# FT232_BreakOutBoard.net
KiCad netlist of a schematic drawn in EAGLE
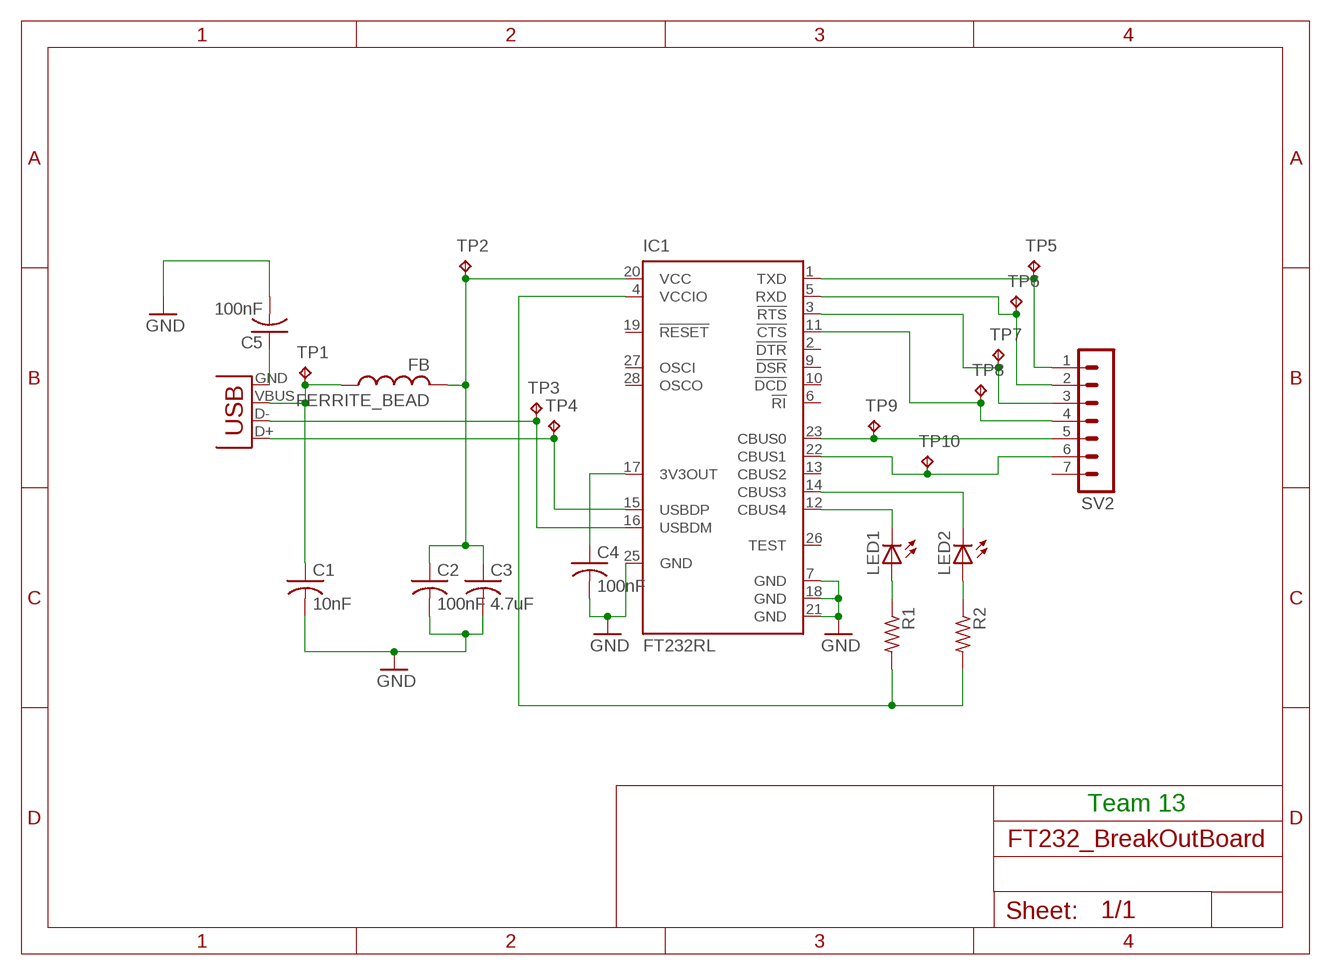
[diagram p0: schematic, sheet 1]

(export (version "E")
  (design (tool "Eeschema 10.0.6"))
  (components
    (comp (ref "C1")
      (value "10nF")
      (footprint "eagle-import:C0805")
      (libsource (lib "eagle-import") (part "C-USC0805"))
    )
    (comp (ref "C2")
      (value "100nF")
      (footprint "eagle-import:C0805")
      (libsource (lib "eagle-import") (part "C-USC0805"))
    )
    (comp (ref "C3")
      (value "4.7uF")
      (footprint "eagle-import:C0805")
      (libsource (lib "eagle-import") (part "C-USC0805"))
    )
    (comp (ref "C4")
      (value "100nF")
      (footprint "eagle-import:C0805")
      (libsource (lib "eagle-import") (part "C-USC0805"))
    )
    (comp (ref "C5")
      (value "100nF")
      (footprint "eagle-import:C0805")
      (libsource (lib "eagle-import") (part "C-USC0805"))
    )
    (comp (ref "FERRITE_BEAD")
      (value "FB")
      (footprint "eagle-import:FB")
      (libsource (lib "eagle-import") (part "FB"))
    )
    (comp (ref "IC1")
      (value "FT232RL")
      (footprint "eagle-import:SSOP28")
      (libsource (lib "eagle-import") (part "FT232RL"))
    )
    (comp (ref "LED1")
      (value "LEDCHIPLED_0805")
      (footprint "eagle-import:CHIPLED_0805")
      (libsource (lib "eagle-import") (part "LEDCHIPLED_0805"))
    )
    (comp (ref "LED2")
      (value "LEDCHIPLED_0805")
      (footprint "eagle-import:CHIPLED_0805")
      (libsource (lib "eagle-import") (part "LEDCHIPLED_0805"))
    )
    (comp (ref "R1")
      (value "R-US_R0805")
      (footprint "eagle-import:R0805")
      (libsource (lib "eagle-import") (part "R-US_R0805"))
    )
    (comp (ref "R2")
      (value "R-US_R0805")
      (footprint "eagle-import:R0805")
      (libsource (lib "eagle-import") (part "R-US_R0805"))
    )
    (comp (ref "SV2")
      (value "MA07-1")
      (footprint "eagle-import:MA07-1")
      (libsource (lib "eagle-import") (part "MA07-1"))
    )
    (comp (ref "TP1")
      (value "TPB1,27")
      (footprint "eagle-import:B1,27")
      (libsource (lib "eagle-import") (part "TPB1,27"))
    )
    (comp (ref "TP2")
      (value "TPB1,27")
      (footprint "eagle-import:B1,27")
      (libsource (lib "eagle-import") (part "TPB1,27"))
    )
    (comp (ref "TP3")
      (value "TPB1,27")
      (footprint "eagle-import:B1,27")
      (libsource (lib "eagle-import") (part "TPB1,27"))
    )
    (comp (ref "TP4")
      (value "TPB1,27")
      (footprint "eagle-import:B1,27")
      (libsource (lib "eagle-import") (part "TPB1,27"))
    )
    (comp (ref "TP5")
      (value "TPB1,27")
      (footprint "eagle-import:B1,27")
      (libsource (lib "eagle-import") (part "TPB1,27"))
    )
    (comp (ref "TP6")
      (value "TPB1,27")
      (footprint "eagle-import:B1,27")
      (libsource (lib "eagle-import") (part "TPB1,27"))
    )
    (comp (ref "TP7")
      (value "TPB1,27")
      (footprint "eagle-import:B1,27")
      (libsource (lib "eagle-import") (part "TPB1,27"))
    )
    (comp (ref "TP8")
      (value "TPB1,27")
      (footprint "eagle-import:B1,27")
      (libsource (lib "eagle-import") (part "TPB1,27"))
    )
    (comp (ref "TP9")
      (value "TPB1,27")
      (footprint "eagle-import:B1,27")
      (libsource (lib "eagle-import") (part "TPB1,27"))
    )
    (comp (ref "TP10")
      (value "TPB1,27")
      (footprint "eagle-import:B1,27")
      (libsource (lib "eagle-import") (part "TPB1,27"))
    )
    (comp (ref "X1")
      (value "USB-B-H")
      (footprint "eagle-import:USB-B-H")
      (libsource (lib "eagle-import") (part "USB-B-H"))
    )
  )
  (nets
    (net (code "1") (name "GND") (class "Default")
      (node (ref "C1") (pin "2") (pinfunction "2_2") (pintype "passive"))
      (node (ref "C2") (pin "2") (pinfunction "2_2") (pintype "passive"))
      (node (ref "C3") (pin "2") (pinfunction "2_2") (pintype "passive"))
      (node (ref "C4") (pin "2") (pinfunction "2_2") (pintype "passive"))
      (node (ref "C5") (pin "2") (pinfunction "2_2") (pintype "passive"))
      (node (ref "IC1") (pin "18") (pinfunction "GND_18") (pintype "power_in"))
      (node (ref "IC1") (pin "21") (pinfunction "GND_21") (pintype "power_in"))
      (node (ref "IC1") (pin "25") (pinfunction "GND_25") (pintype "power_in"))
      (node (ref "IC1") (pin "7") (pinfunction "GND_7") (pintype "power_in"))
    )
    (net (code "2") (name "Net-(C5-Pad1)") (class "Default")
      (node (ref "C5") (pin "1") (pinfunction "1_1") (pintype "passive"))
      (node (ref "X1") (pin "GND") (pinfunction "GND_GND") (pintype "bidirectional"))
    )
    (net (code "3") (name "Net-(FERRITE_BEAD-1)") (class "Default")
      (node (ref "C1") (pin "1") (pinfunction "1_1") (pintype "passive"))
      (node (ref "FERRITE_BEAD") (pin "P$1") (pinfunction "1_P$1") (pintype "passive"))
      (node (ref "TP1") (pin "TP") (pinfunction "TP_TP") (pintype "input"))
      (node (ref "X1") (pin "VBUS") (pinfunction "VBUS_VBUS") (pintype "bidirectional"))
    )
    (net (code "4") (name "Net-(FERRITE_BEAD-2)") (class "Default")
      (node (ref "C2") (pin "1") (pinfunction "1_1") (pintype "passive"))
      (node (ref "C3") (pin "1") (pinfunction "1_1") (pintype "passive"))
      (node (ref "FERRITE_BEAD") (pin "P$2") (pinfunction "2_P$2") (pintype "passive"))
      (node (ref "IC1") (pin "20") (pinfunction "VCC_20") (pintype "power_in"))
      (node (ref "TP2") (pin "TP") (pinfunction "TP_TP") (pintype "input"))
    )
    (net (code "5") (name "Net-(IC1-3V3OUT)") (class "Default")
      (node (ref "C4") (pin "1") (pinfunction "1_1") (pintype "passive"))
      (node (ref "IC1") (pin "17") (pinfunction "3V3OUT_17") (pintype "output"))
    )
    (net (code "6") (name "Net-(IC1-CBUS0)") (class "Default")
      (node (ref "IC1") (pin "23") (pinfunction "CBUS0_23") (pintype "bidirectional"))
      (node (ref "SV2") (pin "5") (pinfunction "5_5") (pintype "passive"))
      (node (ref "TP9") (pin "TP") (pinfunction "TP_TP") (pintype "input"))
    )
    (net (code "7") (name "Net-(IC1-CBUS1)") (class "Default")
      (node (ref "IC1") (pin "22") (pinfunction "CBUS1_22") (pintype "bidirectional"))
      (node (ref "SV2") (pin "6") (pinfunction "6_6") (pintype "passive"))
      (node (ref "TP10") (pin "TP") (pinfunction "TP_TP") (pintype "input"))
    )
    (net (code "8") (name "Net-(IC1-CBUS3)") (class "Default")
      (node (ref "IC1") (pin "14") (pinfunction "CBUS3_14") (pintype "bidirectional"))
      (node (ref "LED2") (pin "C") (pinfunction "C_C") (pintype "passive"))
    )
    (net (code "9") (name "Net-(IC1-CBUS4)") (class "Default")
      (node (ref "IC1") (pin "12") (pinfunction "CBUS4_12") (pintype "bidirectional"))
      (node (ref "LED1") (pin "C") (pinfunction "C_C") (pintype "passive"))
    )
    (net (code "10") (name "Net-(IC1-RXD)") (class "Default")
      (node (ref "IC1") (pin "5") (pinfunction "RXD_5") (pintype "input"))
      (node (ref "SV2") (pin "2") (pinfunction "2_2") (pintype "passive"))
      (node (ref "TP6") (pin "TP") (pinfunction "TP_TP") (pintype "input"))
    )
    (net (code "11") (name "Net-(IC1-TXD)") (class "Default")
      (node (ref "IC1") (pin "1") (pinfunction "TXD_1") (pintype "output"))
      (node (ref "SV2") (pin "1") (pinfunction "1_1") (pintype "passive"))
      (node (ref "TP5") (pin "TP") (pinfunction "TP_TP") (pintype "input"))
    )
    (net (code "12") (name "Net-(IC1-USBDM)") (class "Default")
      (node (ref "IC1") (pin "16") (pinfunction "USBDM_16") (pintype "bidirectional"))
      (node (ref "TP3") (pin "TP") (pinfunction "TP_TP") (pintype "input"))
      (node (ref "X1") (pin "D-") (pinfunction "D-_D-") (pintype "bidirectional"))
    )
    (net (code "13") (name "Net-(IC1-USBDP)") (class "Default")
      (node (ref "IC1") (pin "15") (pinfunction "USBDP_15") (pintype "bidirectional"))
      (node (ref "TP4") (pin "TP") (pinfunction "TP_TP") (pintype "input"))
      (node (ref "X1") (pin "D+") (pinfunction "D+_D+") (pintype "bidirectional"))
    )
    (net (code "14") (name "Net-(IC1-VCCIO)") (class "Default")
      (node (ref "IC1") (pin "4") (pinfunction "VCCIO_4") (pintype "power_in"))
      (node (ref "R1") (pin "2") (pinfunction "2_2") (pintype "passive"))
      (node (ref "R2") (pin "2") (pinfunction "2_2") (pintype "passive"))
    )
    (net (code "15") (name "Net-(IC1-~{CTS})") (class "Default")
      (node (ref "IC1") (pin "11") (pinfunction "~{CTS}_11") (pintype "input"))
      (node (ref "SV2") (pin "4") (pinfunction "4_4") (pintype "passive"))
      (node (ref "TP8") (pin "TP") (pinfunction "TP_TP") (pintype "input"))
    )
    (net (code "16") (name "Net-(IC1-~{RTS})") (class "Default")
      (node (ref "IC1") (pin "3") (pinfunction "~{RTS}_3") (pintype "output"))
      (node (ref "SV2") (pin "3") (pinfunction "3_3") (pintype "passive"))
      (node (ref "TP7") (pin "TP") (pinfunction "TP_TP") (pintype "input"))
    )
    (net (code "17") (name "Net-(LED1-PadA)") (class "Default")
      (node (ref "LED1") (pin "A") (pinfunction "A_A") (pintype "passive"))
      (node (ref "R1") (pin "1") (pinfunction "1_1") (pintype "passive"))
    )
    (net (code "18") (name "Net-(LED2-PadA)") (class "Default")
      (node (ref "LED2") (pin "A") (pinfunction "A_A") (pintype "passive"))
      (node (ref "R2") (pin "1") (pinfunction "1_1") (pintype "passive"))
    )
    (net (code "19") (name "unconnected-(IC1-CBUS2-Pad13)") (class "Default")
      (node (ref "IC1") (pin "13") (pinfunction "CBUS2_13") (pintype "bidirectional"))
    )
    (net (code "20") (name "unconnected-(IC1-OSCI-Pad27)") (class "Default")
      (node (ref "IC1") (pin "27") (pinfunction "OSCI_27") (pintype "input"))
    )
    (net (code "21") (name "unconnected-(IC1-OSCO-Pad28)") (class "Default")
      (node (ref "IC1") (pin "28") (pinfunction "OSCO_28") (pintype "output"))
    )
    (net (code "22") (name "unconnected-(IC1-TEST-Pad26)") (class "Default")
      (node (ref "IC1") (pin "26") (pinfunction "TEST_26") (pintype "input"))
    )
    (net (code "23") (name "unconnected-(IC1-~{DCD}-Pad10)") (class "Default")
      (node (ref "IC1") (pin "10") (pinfunction "~{DCD}_10") (pintype "input"))
    )
    (net (code "24") (name "unconnected-(IC1-~{DSR}-Pad9)") (class "Default")
      (node (ref "IC1") (pin "9") (pinfunction "~{DSR}_9") (pintype "input"))
    )
    (net (code "25") (name "unconnected-(IC1-~{DTR}-Pad2)") (class "Default")
      (node (ref "IC1") (pin "2") (pinfunction "~{DTR}_2") (pintype "output"))
    )
    (net (code "26") (name "unconnected-(IC1-~{RESET}-Pad19)") (class "Default")
      (node (ref "IC1") (pin "19") (pinfunction "~{RESET}_19") (pintype "input"))
    )
    (net (code "27") (name "unconnected-(IC1-~{RI}-Pad6)") (class "Default")
      (node (ref "IC1") (pin "6") (pinfunction "~{RI}_6") (pintype "input"))
    )
    (net (code "28") (name "unconnected-(SV2-Pad7)") (class "Default")
      (node (ref "SV2") (pin "7") (pinfunction "7_7") (pintype "passive"))
    )
  )
)
